# SupportESP8266.net
KiCad netlist of a schematic drawn in EAGLE
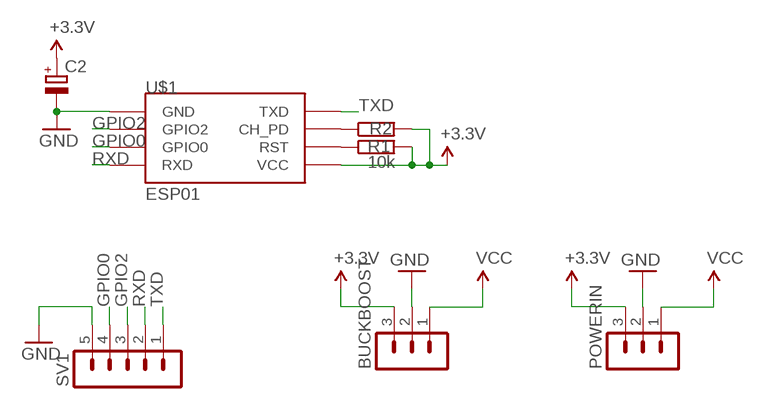
[diagram p0: schematic, sheet 1]

(export (version "E")
  (design (tool "Eeschema 10.0.6"))
  (components
    (comp (ref "BUCKBOOST")
      (value "MA03-1")
      (footprint "eagle-import:MA03-1")
      (libsource (lib "eagle-import") (part "MA03-1"))
    )
    (comp (ref "C2")
      (value "CPOL-EUE5-10.5")
      (footprint "eagle-import:E5-10,5")
      (libsource (lib "eagle-import") (part "CPOL-EUE5-10.5"))
    )
    (comp (ref "POWERIN")
      (value "MA03-1")
      (footprint "eagle-import:MA03-1")
      (libsource (lib "eagle-import") (part "MA03-1"))
    )
    (comp (ref "R1")
      (value "10k")
      (footprint "eagle-import:0204_7")
      (libsource (lib "eagle-import") (part "R-EU_0204/7"))
    )
    (comp (ref "R2")
      (value "R-EU_0204/7")
      (footprint "eagle-import:0204_7")
      (libsource (lib "eagle-import") (part "R-EU_0204/7"))
    )
    (comp (ref "SV1")
      (value "MA05-1")
      (footprint "eagle-import:MA05-1")
      (libsource (lib "eagle-import") (part "MA05-1"))
    )
    (comp (ref "U$1")
      (value "ESP01")
      (footprint "eagle-import:ESP01")
      (libsource (lib "eagle-import") (part "ESP01"))
    )
  )
  (nets
    (net (code "1") (name "+3.3V") (class "Default")
      (node (ref "BUCKBOOST") (pin "3") (pinfunction "3_3") (pintype "passive"))
      (node (ref "C2") (pin "+") (pinfunction "+_+") (pintype "passive"))
      (node (ref "POWERIN") (pin "3") (pinfunction "3_3") (pintype "passive"))
      (node (ref "R1") (pin "2") (pinfunction "2_2") (pintype "passive"))
      (node (ref "R2") (pin "2") (pinfunction "2_2") (pintype "passive"))
      (node (ref "U$1") (pin "VCC") (pinfunction "VCC_VCC") (pintype "bidirectional"))
    )
    (net (code "2") (name "/GPIO0") (class "Default")
      (node (ref "SV1") (pin "4") (pinfunction "4_4") (pintype "passive"))
      (node (ref "U$1") (pin "GPIO0") (pinfunction "GPIO0_GPIO0") (pintype "bidirectional"))
    )
    (net (code "3") (name "/GPIO2") (class "Default")
      (node (ref "SV1") (pin "3") (pinfunction "3_3") (pintype "passive"))
      (node (ref "U$1") (pin "GPIO2") (pinfunction "GPIO2_GPIO2") (pintype "bidirectional"))
    )
    (net (code "4") (name "/RXD") (class "Default")
      (node (ref "SV1") (pin "2") (pinfunction "2_2") (pintype "passive"))
      (node (ref "U$1") (pin "RX") (pinfunction "RXD_RX") (pintype "bidirectional"))
    )
    (net (code "5") (name "/TXD") (class "Default")
      (node (ref "SV1") (pin "1") (pinfunction "1_1") (pintype "passive"))
      (node (ref "U$1") (pin "TX") (pinfunction "TXD_TX") (pintype "bidirectional"))
    )
    (net (code "6") (name "GND") (class "Default")
      (node (ref "BUCKBOOST") (pin "2") (pinfunction "2_2") (pintype "passive"))
      (node (ref "C2") (pin "-") (pinfunction "-_-") (pintype "passive"))
      (node (ref "POWERIN") (pin "2") (pinfunction "2_2") (pintype "passive"))
      (node (ref "SV1") (pin "5") (pinfunction "5_5") (pintype "passive"))
      (node (ref "U$1") (pin "GND") (pinfunction "GND_GND") (pintype "bidirectional"))
    )
    (net (code "7") (name "Net-(R1-Pad1)") (class "Default")
      (node (ref "R1") (pin "1") (pinfunction "1_1") (pintype "passive"))
      (node (ref "U$1") (pin "RST") (pinfunction "RST_RST") (pintype "bidirectional"))
    )
    (net (code "8") (name "Net-(R2-Pad1)") (class "Default")
      (node (ref "R2") (pin "1") (pinfunction "1_1") (pintype "passive"))
      (node (ref "U$1") (pin "CH_PD") (pinfunction "CH_PD_CH_PD") (pintype "bidirectional"))
    )
    (net (code "9") (name "VCC") (class "Default")
      (node (ref "BUCKBOOST") (pin "1") (pinfunction "1_1") (pintype "passive"))
      (node (ref "POWERIN") (pin "1") (pinfunction "1_1") (pintype "passive"))
    )
  )
)
